# wetterstation_easyeda.net
KiCad netlist of a schematic drawn in EasyEDA
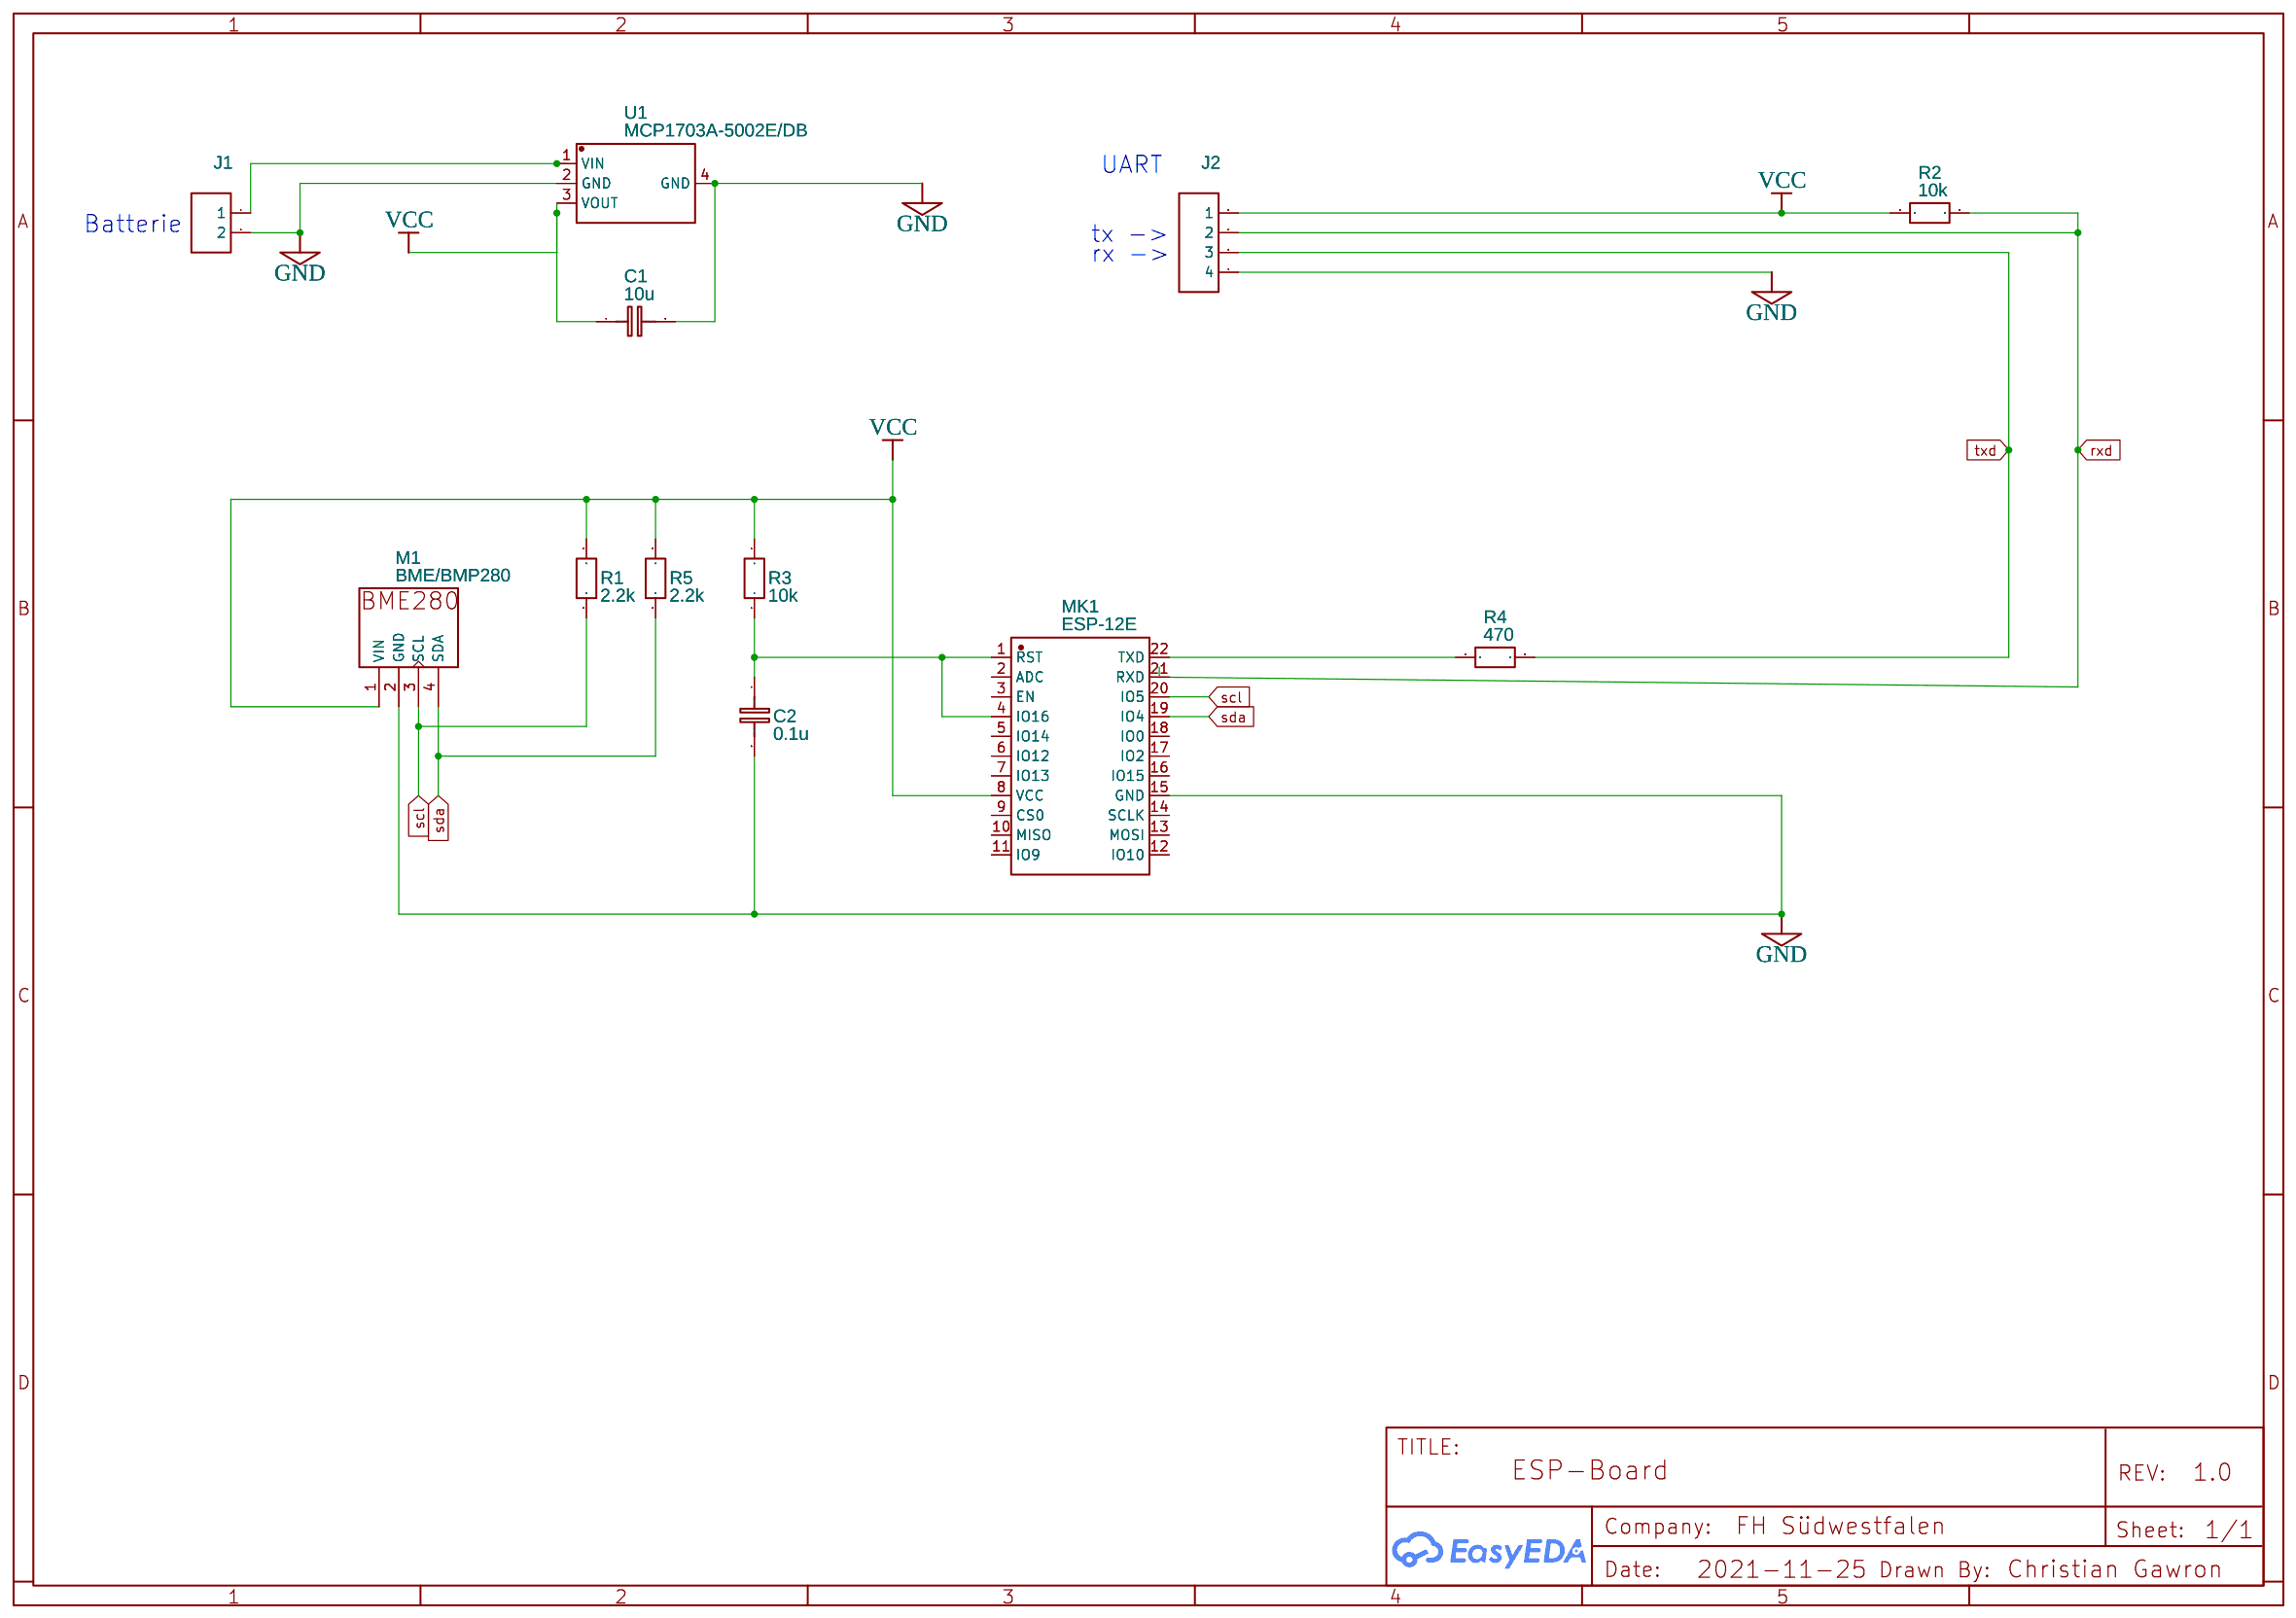
[diagram p0: schematic sheet]

(export (version "E")
  (design (tool "Eeschema 10.0.6"))
  (components
    (comp (ref "C1") (value "10u") (libsource (lib "") (part "C_0603_EU")))
    (comp (ref "C2") (value "0.1u") (libsource (lib "") (part "C_0805_EU")))
    (comp (ref "J1")
      (value "HDR-M-2.54_1x2")
      (fields (field (name "BOM_Supplier Part") "C124375"))
      (libsource (lib "") (part "HDR-M-2.54_1x2"))
    )
    (comp (ref "J2")
      (value "HDR-M-2.54_1x4")
      (fields (field (name "BOM_Supplier Part") "C124378"))
      (libsource (lib "") (part "HDR-M-2.54_1x4"))
    )
    (comp (ref "M1") (value "BME/BMP280") (libsource (lib "") (part "BME/BMP280")))
    (comp (ref "MK1")
      (value "ESP-12E")
      (fields (field (name "BOM_Supplier Part") "C89297"))
      (libsource (lib "") (part "ESP-12E"))
    )
    (comp (ref "R1") (value "2.2k") (libsource (lib "") (part "R_0603_EU")))
    (comp (ref "R2") (value "10k") (libsource (lib "") (part "R_0603_EU_1")))
    (comp (ref "R3") (value "10k") (libsource (lib "") (part "R_0603_EU")))
    (comp (ref "R4") (value "470") (libsource (lib "") (part "R_0603_EU_1")))
    (comp (ref "R5") (value "2.2k") (libsource (lib "") (part "R_0603_EU")))
    (comp (ref "U1")
      (value "MCP1703A-5002E/DB")
      (fields (field (name "BOM_Supplier Part") "C185652"))
      (libsource (lib "") (part "MCP1703A-5002E/DB"))
    )
  )
  (nets
    (net (code "1") (name "GND") (class "Default")
      (node (ref "C1") (pin "2") (pinfunction "2_2") (pintype "unspecified"))
      (node (ref "C2") (pin "2") (pinfunction "2_2") (pintype "unspecified"))
      (node (ref "J1") (pin "2") (pinfunction "2_2") (pintype "unspecified"))
      (node (ref "J2") (pin "4") (pinfunction "4_4") (pintype "unspecified"))
      (node (ref "M1") (pin "2") (pinfunction "GND_2") (pintype "unspecified"))
      (node (ref "MK1") (pin "15") (pinfunction "GND_15") (pintype "unspecified"))
      (node (ref "U1") (pin "2") (pinfunction "GND_2") (pintype "unspecified"))
      (node (ref "U1") (pin "4") (pinfunction "GND_4") (pintype "unspecified"))
    )
    (net (code "2") (name "Net-(MK1-IO16)") (class "Default")
      (node (ref "C2") (pin "1") (pinfunction "1_1") (pintype "unspecified"))
      (node (ref "MK1") (pin "1") (pinfunction "RST_1") (pintype "unspecified"))
      (node (ref "MK1") (pin "4") (pinfunction "IO16_4") (pintype "unspecified"))
      (node (ref "R3") (pin "1") (pinfunction "1_1") (pintype "unspecified"))
    )
    (net (code "3") (name "Net-(MK1-TXD)") (class "Default")
      (node (ref "MK1") (pin "22") (pinfunction "TXD_22") (pintype "unspecified"))
      (node (ref "R4") (pin "1") (pinfunction "1_1") (pintype "unspecified"))
    )
    (net (code "4") (name "Net-(U1-VIN)") (class "Default")
      (node (ref "J1") (pin "1") (pinfunction "1_1") (pintype "unspecified"))
      (node (ref "U1") (pin "1") (pinfunction "VIN_1") (pintype "unspecified"))
    )
    (net (code "5") (name "VCC") (class "Default")
      (node (ref "C1") (pin "1") (pinfunction "1_1") (pintype "unspecified"))
      (node (ref "J2") (pin "1") (pinfunction "1_1") (pintype "unspecified"))
      (node (ref "M1") (pin "1") (pinfunction "VIN_1") (pintype "unspecified"))
      (node (ref "MK1") (pin "8") (pinfunction "VCC_8") (pintype "unspecified"))
      (node (ref "R1") (pin "2") (pinfunction "2_2") (pintype "unspecified"))
      (node (ref "R2") (pin "1") (pinfunction "1_1") (pintype "unspecified"))
      (node (ref "R3") (pin "2") (pinfunction "2_2") (pintype "unspecified"))
      (node (ref "R5") (pin "2") (pinfunction "2_2") (pintype "unspecified"))
      (node (ref "U1") (pin "3") (pinfunction "VOUT_3") (pintype "unspecified"))
    )
    (net (code "6") (name "rxd") (class "Default")
      (node (ref "J2") (pin "2") (pinfunction "2_2") (pintype "unspecified"))
      (node (ref "R2") (pin "2") (pinfunction "2_2") (pintype "unspecified"))
    )
    (net (code "7") (name "scl") (class "Default")
      (node (ref "M1") (pin "3") (pinfunction "SCL_3") (pintype "unspecified"))
      (node (ref "MK1") (pin "20") (pinfunction "IO5_20") (pintype "unspecified"))
      (node (ref "R1") (pin "1") (pinfunction "1_1") (pintype "unspecified"))
    )
    (net (code "8") (name "sda") (class "Default")
      (node (ref "M1") (pin "4") (pinfunction "SDA_4") (pintype "unspecified"))
      (node (ref "MK1") (pin "19") (pinfunction "IO4_19") (pintype "unspecified"))
      (node (ref "R5") (pin "1") (pinfunction "1_1") (pintype "unspecified"))
    )
    (net (code "9") (name "txd") (class "Default")
      (node (ref "J2") (pin "3") (pinfunction "3_3") (pintype "unspecified"))
      (node (ref "R4") (pin "2") (pinfunction "2_2") (pintype "unspecified"))
    )
    (net (code "10") (name "unconnected-(MK1-ADC-Pad2)") (class "Default")
      (node (ref "MK1") (pin "2") (pinfunction "ADC_2") (pintype "unspecified"))
    )
    (net (code "11") (name "unconnected-(MK1-CS0-Pad9)") (class "Default")
      (node (ref "MK1") (pin "9") (pinfunction "CS0_9") (pintype "unspecified"))
    )
    (net (code "12") (name "unconnected-(MK1-EN-Pad3)") (class "Default")
      (node (ref "MK1") (pin "3") (pinfunction "EN_3") (pintype "unspecified"))
    )
    (net (code "13") (name "unconnected-(MK1-IO0-Pad18)") (class "Default")
      (node (ref "MK1") (pin "18") (pinfunction "IO0_18") (pintype "unspecified"))
    )
    (net (code "14") (name "unconnected-(MK1-IO2-Pad17)") (class "Default")
      (node (ref "MK1") (pin "17") (pinfunction "IO2_17") (pintype "unspecified"))
    )
    (net (code "15") (name "unconnected-(MK1-IO9-Pad11)") (class "Default")
      (node (ref "MK1") (pin "11") (pinfunction "IO9_11") (pintype "unspecified"))
    )
    (net (code "16") (name "unconnected-(MK1-IO10-Pad12)") (class "Default")
      (node (ref "MK1") (pin "12") (pinfunction "IO10_12") (pintype "unspecified"))
    )
    (net (code "17") (name "unconnected-(MK1-IO12-Pad6)") (class "Default")
      (node (ref "MK1") (pin "6") (pinfunction "IO12_6") (pintype "unspecified"))
    )
    (net (code "18") (name "unconnected-(MK1-IO13-Pad7)") (class "Default")
      (node (ref "MK1") (pin "7") (pinfunction "IO13_7") (pintype "unspecified"))
    )
    (net (code "19") (name "unconnected-(MK1-IO14-Pad5)") (class "Default")
      (node (ref "MK1") (pin "5") (pinfunction "IO14_5") (pintype "unspecified"))
    )
    (net (code "20") (name "unconnected-(MK1-IO15-Pad16)") (class "Default")
      (node (ref "MK1") (pin "16") (pinfunction "IO15_16") (pintype "unspecified"))
    )
    (net (code "21") (name "unconnected-(MK1-MISO-Pad10)") (class "Default")
      (node (ref "MK1") (pin "10") (pinfunction "MISO_10") (pintype "unspecified"))
    )
    (net (code "22") (name "unconnected-(MK1-MOSI-Pad13)") (class "Default")
      (node (ref "MK1") (pin "13") (pinfunction "MOSI_13") (pintype "unspecified"))
    )
    (net (code "23") (name "unconnected-(MK1-RXD-Pad21)") (class "Default")
      (node (ref "MK1") (pin "21") (pinfunction "RXD_21") (pintype "unspecified"))
    )
    (net (code "24") (name "unconnected-(MK1-SCLK-Pad14)") (class "Default")
      (node (ref "MK1") (pin "14") (pinfunction "SCLK_14") (pintype "unspecified"))
    )
  )
)
